# MS5803-14BA_Breakout.net
KiCad netlist of a schematic drawn in EAGLE
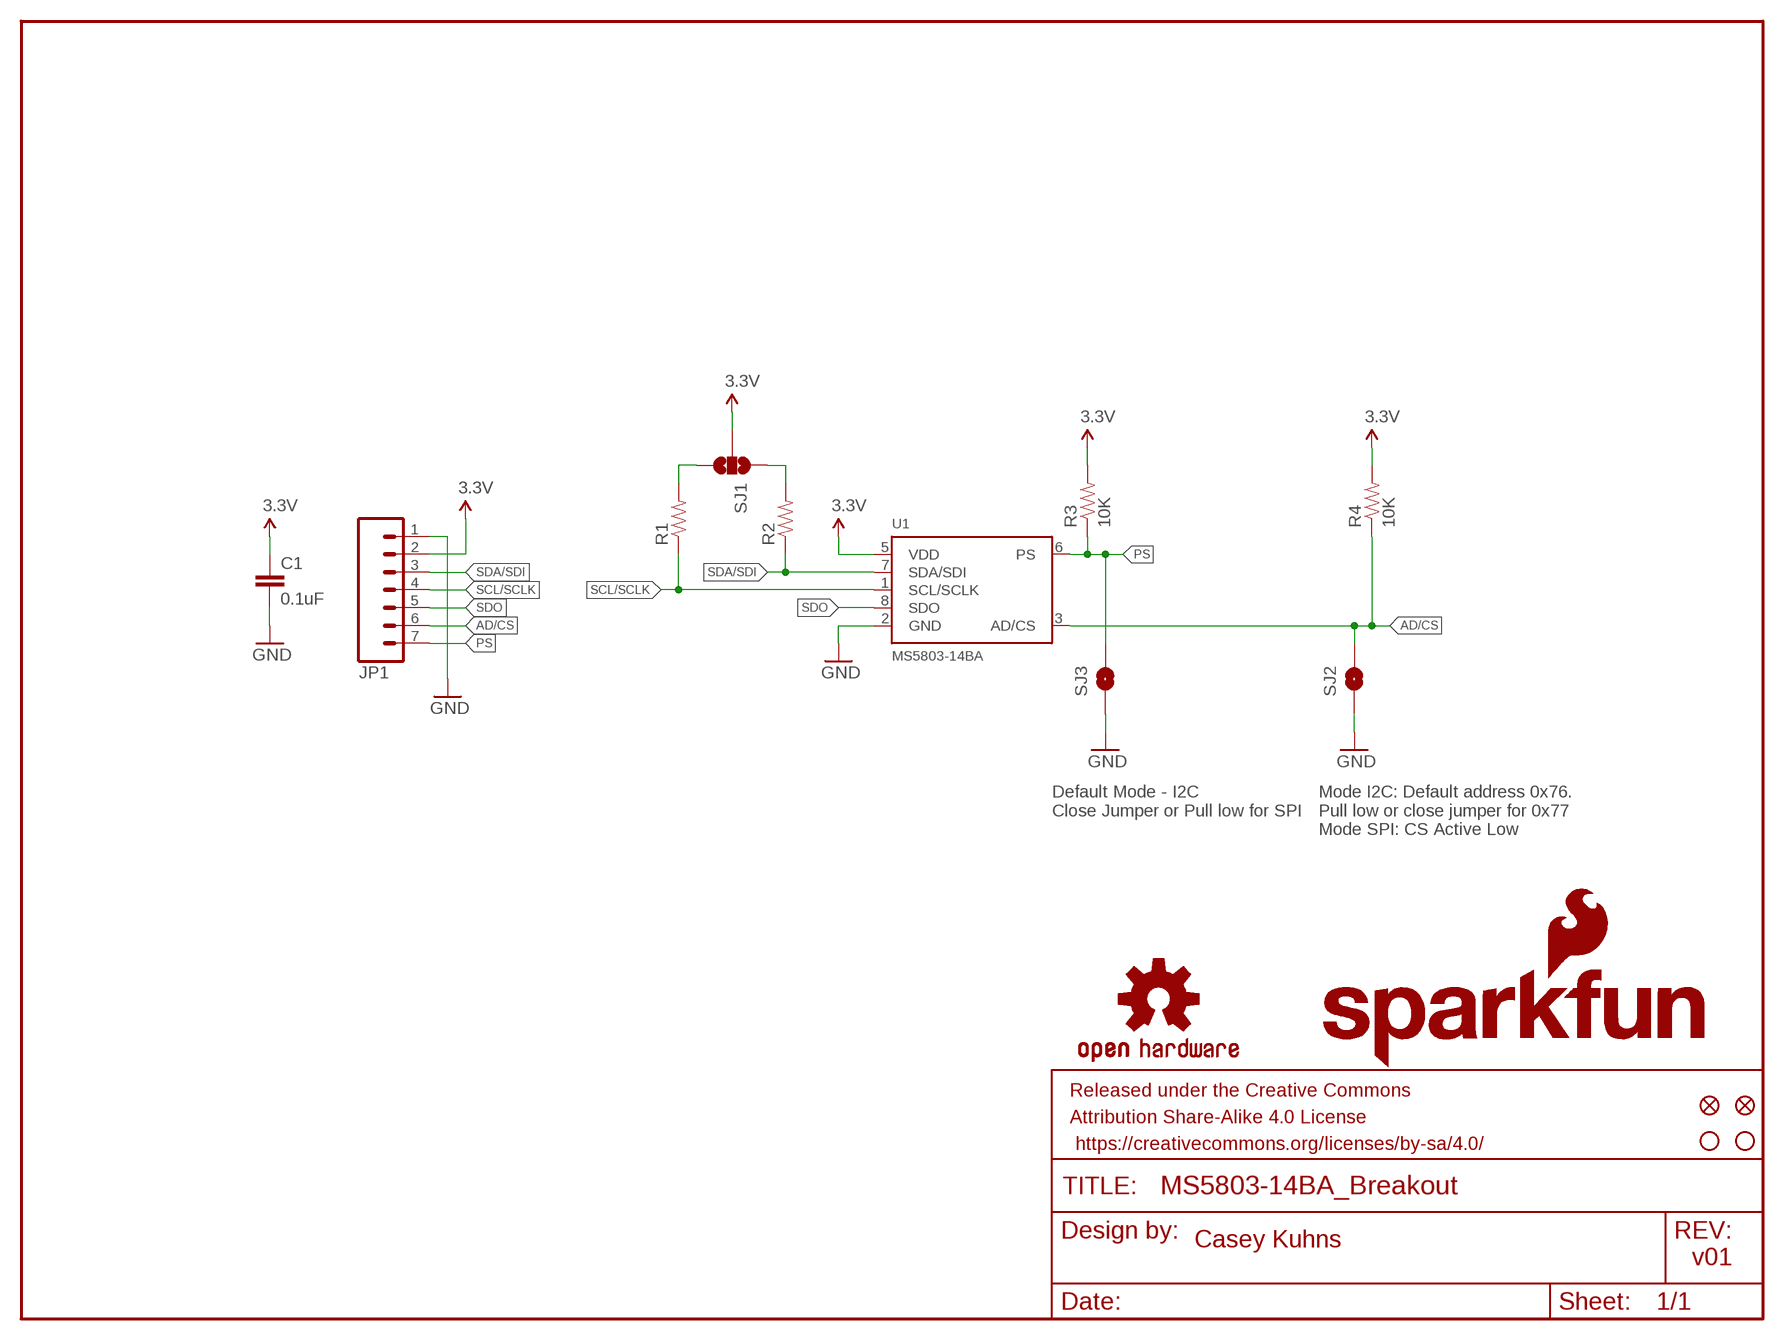
[diagram p0: schematic, sheet 1]

(export (version "E")
  (design (tool "Eeschema 10.0.6"))
  (components
    (comp (ref "C1")
      (value "0.1uF")
      (footprint "eagle-import:0603-CAP")
      (libsource (lib "eagle-import") (part "0.1UF-25V(+80/-20%)(0603)"))
    )
    (comp (ref "FID1")
      (value "FIDUCIAL1X2")
      (footprint "eagle-import:FIDUCIAL-1X2")
      (libsource (lib "eagle-import") (part "FIDUCIAL1X2"))
    )
    (comp (ref "FID2")
      (value "FIDUCIAL1X2")
      (footprint "eagle-import:FIDUCIAL-1X2")
      (libsource (lib "eagle-import") (part "FIDUCIAL1X2"))
    )
    (comp (ref "FRAME1")
      (value "FRAME-LETTER")
      (footprint "eagle-import:CREATIVE_COMMONS")
      (libsource (lib "eagle-import") (part "FRAME-LETTER"))
    )
    (comp (ref "JP1")
      (value "M07")
      (footprint "eagle-import:1X07")
      (libsource (lib "eagle-import") (part "M07"))
    )
    (comp (ref "LOGO1")
      (value "SFE_LOGO_FLAME.1_INCH")
      (footprint "eagle-import:SFE_LOGO_FLAME_.1")
      (libsource (lib "eagle-import") (part "SFE_LOGO_FLAME.1_INCH"))
    )
    (comp (ref "LOGO2")
      (value "SFE_LOGO_NAME_FLAME.1_INCH")
      (footprint "eagle-import:SFE_LOGO_NAME_FLAME_.1")
      (libsource (lib "eagle-import") (part "SFE_LOGO_NAME_FLAME.1_INCH"))
    )
    (comp (ref "LOGO3")
      (value "OSHW-LOGOS")
      (footprint "eagle-import:OSHW-LOGO-S")
      (libsource (lib "eagle-import") (part "OSHW-LOGOS"))
    )
    (comp (ref "R1")
      (value "4.7KOHM1/10W1%(0603)")
      (footprint "eagle-import:0603")
      (libsource (lib "eagle-import") (part "4.7KOHM1/10W1%(0603)"))
    )
    (comp (ref "R2")
      (value "4.7KOHM1/10W1%(0603)")
      (footprint "eagle-import:0603")
      (libsource (lib "eagle-import") (part "4.7KOHM1/10W1%(0603)"))
    )
    (comp (ref "R3")
      (value "10K")
      (footprint "eagle-import:0603-RES")
      (libsource (lib "eagle-import") (part "10KOHM1/10W1%(0603)0603"))
    )
    (comp (ref "R4")
      (value "10K")
      (footprint "eagle-import:0603-RES")
      (libsource (lib "eagle-import") (part "10KOHM1/10W1%(0603)0603"))
    )
    (comp (ref "SJ1")
      (value "SOLDERJUMPER_2WAYPASTE1&2&3")
      (footprint "eagle-import:SJ_3_PASTE1&2&3")
      (libsource (lib "eagle-import") (part "SOLDERJUMPER_2WAYPASTE1&2&3"))
    )
    (comp (ref "SJ2")
      (value "SOLDERJUMPERNO")
      (footprint "eagle-import:SJ_2S-NO")
      (libsource (lib "eagle-import") (part "SOLDERJUMPERNO"))
    )
    (comp (ref "SJ3")
      (value "SOLDERJUMPERNO")
      (footprint "eagle-import:SJ_2S-NO")
      (libsource (lib "eagle-import") (part "SOLDERJUMPERNO"))
    )
    (comp (ref "STANDOFF1")
      (value "STAND-OFFTIGHT")
      (footprint "eagle-import:STAND-OFF-TIGHT")
      (libsource (lib "eagle-import") (part "STAND-OFFTIGHT"))
    )
    (comp (ref "STANDOFF2")
      (value "STAND-OFFTIGHT")
      (footprint "eagle-import:STAND-OFF-TIGHT")
      (libsource (lib "eagle-import") (part "STAND-OFFTIGHT"))
    )
    (comp (ref "U1")
      (value "MS5803-14BA")
      (footprint "eagle-import:MS5803")
      (libsource (lib "eagle-import") (part "MS5803-14BA"))
    )
  )
  (nets
    (net (code "1") (name "3.3V") (class "Default")
      (node (ref "C1") (pin "1") (pinfunction "1_1") (pintype "passive"))
      (node (ref "JP1") (pin "2") (pinfunction "2_2") (pintype "passive"))
      (node (ref "R3") (pin "2") (pinfunction "2_2") (pintype "passive"))
      (node (ref "R4") (pin "2") (pinfunction "2_2") (pintype "passive"))
      (node (ref "SJ1") (pin "2") (pinfunction "2_2") (pintype "passive"))
      (node (ref "U1") (pin "5") (pinfunction "VDD_5") (pintype "bidirectional"))
    )
    (net (code "2") (name "AD{slash}CS") (class "Default")
      (node (ref "JP1") (pin "6") (pinfunction "6_6") (pintype "passive"))
      (node (ref "R4") (pin "1") (pinfunction "1_1") (pintype "passive"))
      (node (ref "SJ2") (pin "2") (pinfunction "2_2") (pintype "passive"))
      (node (ref "U1") (pin "3") (pinfunction "AD/CS_3") (pintype "bidirectional"))
    )
    (net (code "3") (name "GND") (class "Default")
      (node (ref "C1") (pin "2") (pinfunction "2_2") (pintype "passive"))
      (node (ref "JP1") (pin "1") (pinfunction "1_1") (pintype "passive"))
      (node (ref "SJ2") (pin "1") (pinfunction "1_1") (pintype "passive"))
      (node (ref "SJ3") (pin "1") (pinfunction "1_1") (pintype "passive"))
      (node (ref "U1") (pin "2") (pinfunction "GND_2") (pintype "bidirectional"))
    )
    (net (code "4") (name "Net-(R1-Pad2)") (class "Default")
      (node (ref "R1") (pin "2") (pinfunction "2_2") (pintype "passive"))
      (node (ref "SJ1") (pin "3") (pinfunction "3_3") (pintype "passive"))
    )
    (net (code "5") (name "Net-(R2-Pad2)") (class "Default")
      (node (ref "R2") (pin "2") (pinfunction "2_2") (pintype "passive"))
      (node (ref "SJ1") (pin "1") (pinfunction "1_1") (pintype "passive"))
    )
    (net (code "6") (name "PS") (class "Default")
      (node (ref "JP1") (pin "7") (pinfunction "7_7") (pintype "passive"))
      (node (ref "R3") (pin "1") (pinfunction "1_1") (pintype "passive"))
      (node (ref "SJ3") (pin "2") (pinfunction "2_2") (pintype "passive"))
      (node (ref "U1") (pin "6") (pinfunction "PS_6") (pintype "bidirectional"))
    )
    (net (code "7") (name "SCL{slash}SCLK") (class "Default")
      (node (ref "JP1") (pin "4") (pinfunction "4_4") (pintype "passive"))
      (node (ref "R1") (pin "1") (pinfunction "1_1") (pintype "passive"))
      (node (ref "U1") (pin "1") (pinfunction "SCL/SCLK_1") (pintype "bidirectional"))
    )
    (net (code "8") (name "SDA{slash}SDI") (class "Default")
      (node (ref "JP1") (pin "3") (pinfunction "3_3") (pintype "passive"))
      (node (ref "R2") (pin "1") (pinfunction "1_1") (pintype "passive"))
      (node (ref "U1") (pin "7") (pinfunction "SDA/SDI_7") (pintype "bidirectional"))
    )
    (net (code "9") (name "SDO") (class "Default")
      (node (ref "JP1") (pin "5") (pinfunction "5_5") (pintype "passive"))
      (node (ref "U1") (pin "8") (pinfunction "SDO_8") (pintype "bidirectional"))
    )
  )
)
